# ch340_usb.net
KiCad netlist of a schematic drawn in EAGLE
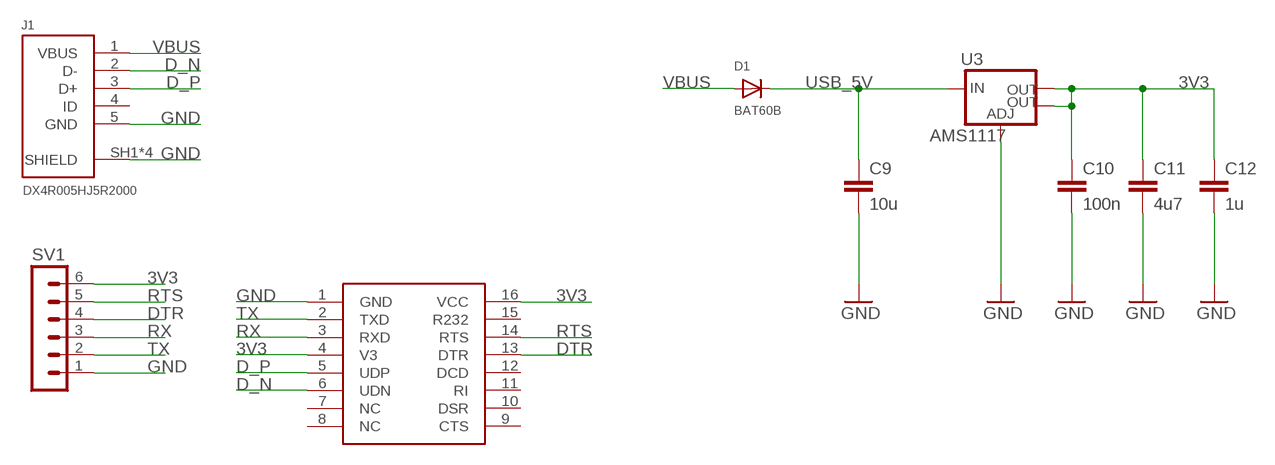
[diagram p0: schematic, sheet 1]

(export (version "E")
  (design (tool "Eeschema 10.0.6"))
  (components
    (comp (ref "C9")
      (value "10u")
      (footprint "eagle-import:C0603")
      (libsource (lib "eagle-import") (part "C-EUC0603"))
    )
    (comp (ref "C10")
      (value "100n")
      (footprint "eagle-import:C0603")
      (libsource (lib "eagle-import") (part "C-EUC0603"))
    )
    (comp (ref "C11")
      (value "4u7")
      (footprint "eagle-import:C0603")
      (libsource (lib "eagle-import") (part "C-EUC0603"))
    )
    (comp (ref "C12")
      (value "1u")
      (footprint "eagle-import:C0603")
      (libsource (lib "eagle-import") (part "C-EUC0603"))
    )
    (comp (ref "D1")
      (value "BAT60B")
      (footprint "eagle-import:SOD-323F")
      (libsource (lib "eagle-import") (part "DIODESOD-323F"))
    )
    (comp (ref "J1")
      (value "DX4R005HJ5R2000")
      (footprint "eagle-import:DX4R005HJ5R2000")
      (fields
        (field (name "DIGIKEY_PARTNO") "670-2674-2-ND")
        (field (name "MANUFACTURER") "JAE Electronics")
        (field (name "CREATED_BY") "PCBLayout.com")
      )
      (libsource (lib "eagle-import") (part "DX4R005HJ5R2000"))
    )
    (comp (ref "SV1")
      (value "MA06-1")
      (footprint "eagle-import:MA06-1")
      (libsource (lib "eagle-import") (part "MA06-1"))
    )
    (comp (ref "U$1")
      (value "CH340")
      (footprint "eagle-import:SOP16")
      (libsource (lib "eagle-import") (part "CH340"))
    )
    (comp (ref "U3")
      (value "AMS1117")
      (footprint "eagle-import:SOT223")
      (libsource (lib "eagle-import") (part "V_REG_LM1117SOT223"))
    )
  )
  (nets
    (net (code "1") (name "/3V3") (class "Default")
      (node (ref "C10") (pin "1") (pinfunction "1_1") (pintype "passive"))
      (node (ref "C11") (pin "1") (pinfunction "1_1") (pintype "passive"))
      (node (ref "C12") (pin "1") (pinfunction "1_1") (pintype "passive"))
      (node (ref "SV1") (pin "6") (pinfunction "6_6") (pintype "passive"))
      (node (ref "U$1") (pin "16") (pinfunction "VCC_16") (pintype "bidirectional"))
      (node (ref "U$1") (pin "4") (pinfunction "V3_4") (pintype "bidirectional"))
      (node (ref "U3") (pin "2") (pinfunction "OUT_2") (pintype "output"))
      (node (ref "U3") (pin "4") (pinfunction "OUT_4") (pintype "output"))
    )
    (net (code "2") (name "/DTR") (class "Default")
      (node (ref "SV1") (pin "4") (pinfunction "4_4") (pintype "passive"))
      (node (ref "U$1") (pin "13") (pinfunction "DTR_13") (pintype "bidirectional"))
    )
    (net (code "3") (name "/D_N") (class "Default")
      (node (ref "J1") (pin "2") (pinfunction "D-_2") (pintype "passive"))
      (node (ref "U$1") (pin "6") (pinfunction "UDN_6") (pintype "bidirectional"))
    )
    (net (code "4") (name "/D_P") (class "Default")
      (node (ref "J1") (pin "3") (pinfunction "D+_3") (pintype "passive"))
      (node (ref "U$1") (pin "5") (pinfunction "UDP_5") (pintype "bidirectional"))
    )
    (net (code "5") (name "/RTS") (class "Default")
      (node (ref "SV1") (pin "5") (pinfunction "5_5") (pintype "passive"))
      (node (ref "U$1") (pin "14") (pinfunction "RTS_14") (pintype "bidirectional"))
    )
    (net (code "6") (name "/RX") (class "Default")
      (node (ref "SV1") (pin "3") (pinfunction "3_3") (pintype "passive"))
      (node (ref "U$1") (pin "3") (pinfunction "RXD_3") (pintype "bidirectional"))
    )
    (net (code "7") (name "/TX") (class "Default")
      (node (ref "SV1") (pin "2") (pinfunction "2_2") (pintype "passive"))
      (node (ref "U$1") (pin "2") (pinfunction "TXD_2") (pintype "bidirectional"))
    )
    (net (code "8") (name "/USB_5V") (class "Default")
      (node (ref "C9") (pin "1") (pinfunction "1_1") (pintype "passive"))
      (node (ref "D1") (pin "C") (pinfunction "C_C") (pintype "passive"))
      (node (ref "U3") (pin "3") (pinfunction "IN_3") (pintype "input"))
    )
    (net (code "9") (name "/VBUS") (class "Default")
      (node (ref "D1") (pin "A") (pinfunction "A_A") (pintype "passive"))
      (node (ref "J1") (pin "1") (pinfunction "VBUS_1") (pintype "passive"))
    )
    (net (code "10") (name "GND") (class "Default")
      (node (ref "C10") (pin "2") (pinfunction "2_2") (pintype "passive"))
      (node (ref "C11") (pin "2") (pinfunction "2_2") (pintype "passive"))
      (node (ref "C12") (pin "2") (pinfunction "2_2") (pintype "passive"))
      (node (ref "C9") (pin "2") (pinfunction "2_2") (pintype "passive"))
      (node (ref "J1") (pin "5") (pinfunction "GND_5") (pintype "passive"))
      (node (ref "J1") (pin "SH1") (pinfunction "SHIELD_SH1") (pintype "power_in"))
      (node (ref "J1") (pin "SH2") (pinfunction "SHIELD_SH2") (pintype "power_in"))
      (node (ref "J1") (pin "SH3") (pinfunction "SHIELD_SH3") (pintype "power_in"))
      (node (ref "J1") (pin "SH4") (pinfunction "SHIELD_SH4") (pintype "power_in"))
      (node (ref "SV1") (pin "1") (pinfunction "1_1") (pintype "passive"))
      (node (ref "U$1") (pin "1") (pinfunction "GND_1") (pintype "bidirectional"))
      (node (ref "U3") (pin "1") (pinfunction "ADJ_1") (pintype "input"))
    )
    (net (code "11") (name "unconnected-(J1-ID-Pad4)") (class "Default")
      (node (ref "J1") (pin "4") (pinfunction "ID_4") (pintype "passive"))
    )
    (net (code "12") (name "unconnected-(U$1-CTS-Pad9)") (class "Default")
      (node (ref "U$1") (pin "9") (pinfunction "CTS_9") (pintype "bidirectional"))
    )
    (net (code "13") (name "unconnected-(U$1-DCD-Pad12)") (class "Default")
      (node (ref "U$1") (pin "12") (pinfunction "DCD_12") (pintype "bidirectional"))
    )
    (net (code "14") (name "unconnected-(U$1-DSR-Pad10)") (class "Default")
      (node (ref "U$1") (pin "10") (pinfunction "DSR_10") (pintype "bidirectional"))
    )
    (net (code "15") (name "unconnected-(U$1-NC-Pad7)") (class "Default")
      (node (ref "U$1") (pin "7") (pinfunction "NC_7") (pintype "bidirectional"))
    )
    (net (code "16") (name "unconnected-(U$1-NC-Pad8)") (class "Default")
      (node (ref "U$1") (pin "8") (pinfunction "NC_8") (pintype "bidirectional"))
    )
    (net (code "17") (name "unconnected-(U$1-R232-Pad15)") (class "Default")
      (node (ref "U$1") (pin "15") (pinfunction "R232_15") (pintype "bidirectional"))
    )
    (net (code "18") (name "unconnected-(U$1-RI-Pad11)") (class "Default")
      (node (ref "U$1") (pin "11") (pinfunction "RI_11") (pintype "bidirectional"))
    )
  )
)
